# LAUNCHXL-F28379D_6.net
KiCad netlist of a schematic drawn in Altium Designer
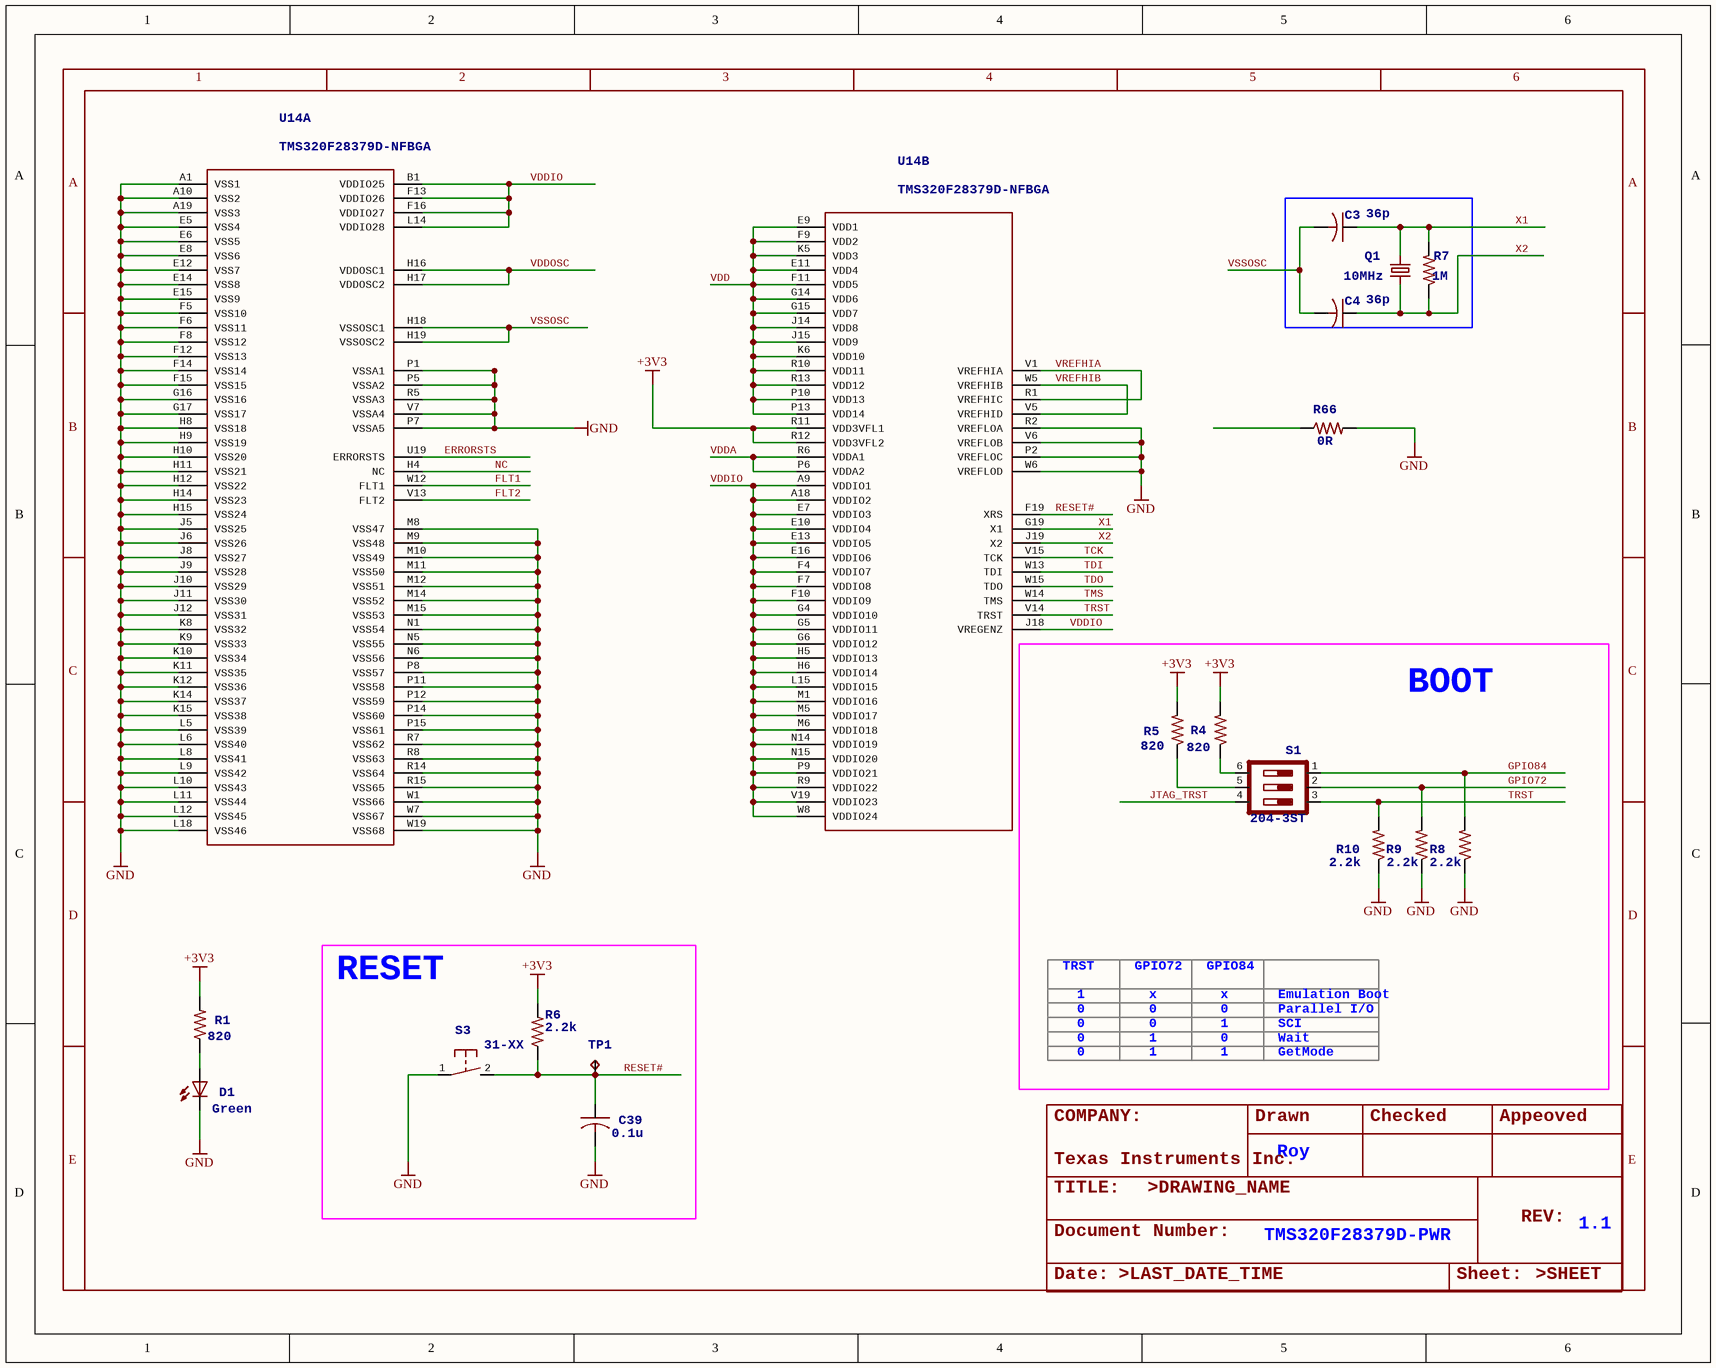
[diagram p0: LAUNCHXL-F28379D_6.SchDoc]

(export (version "E")
  (design (tool "Eeschema 10.0.6"))
  (components
    (comp (ref "C3")
      (value "36p")
      (footprint "C0402")
      (description "<B>CAPACITOR</B>, American symbol")
      (libsource (lib "rcl") (part "C-USC0402"))
    )
    (comp (ref "C4")
      (value "36p")
      (footprint "C0402")
      (description "<B>CAPACITOR</B>, American symbol")
      (libsource (lib "rcl") (part "C-USC0402"))
    )
    (comp (ref "C39")
      (value "0.1u")
      (footprint "C0402")
      (description "<B>CAPACITOR</B>, American symbol")
      (libsource (lib "rcl") (part "C-USC0402"))
    )
    (comp (ref "D1")
      (value "Green")
      (footprint "CHIP-LED0603")
      (libsource (lib "led") (part "LEDCHIP-LED0603"))
    )
    (comp (ref "Q1")
      (value "10MHz")
      (footprint "HC49/S")
      (description "<b>CRYSTAL</b>")
      (libsource (lib "crystal") (part "CRYSTALHC49S"))
    )
    (comp (ref "R1")
      (value "820")
      (footprint "R0402")
      (description "<B>RESISTOR</B>, American symbol")
      (libsource (lib "rcl") (part "R-US_R0402"))
    )
    (comp (ref "R4")
      (value "820")
      (footprint "R0402")
      (description "<B>RESISTOR</B>, American symbol")
      (libsource (lib "rcl") (part "R-US_R0402"))
    )
    (comp (ref "R5")
      (value "820")
      (footprint "R0402")
      (description "<B>RESISTOR</B>, American symbol")
      (libsource (lib "rcl") (part "R-US_R0402"))
    )
    (comp (ref "R6")
      (value "2.2k")
      (footprint "R0402")
      (description "<B>RESISTOR</B>, American symbol")
      (libsource (lib "rcl") (part "R-US_R0402"))
    )
    (comp (ref "R7")
      (value "1M")
      (footprint "R0402")
      (description "<B>RESISTOR</B>, American symbol")
      (libsource (lib "rcl") (part "R-US_R0402"))
    )
    (comp (ref "R8")
      (value "2.2k")
      (footprint "R0402")
      (description "<B>RESISTOR</B>, American symbol")
      (libsource (lib "rcl") (part "R-US_R0402"))
    )
    (comp (ref "R9")
      (value "2.2k")
      (footprint "R0402")
      (description "<B>RESISTOR</B>, American symbol")
      (libsource (lib "rcl") (part "R-US_R0402"))
    )
    (comp (ref "R10")
      (value "2.2k")
      (footprint "R0402")
      (description "<B>RESISTOR</B>, American symbol")
      (libsource (lib "rcl") (part "R-US_R0402"))
    )
    (comp (ref "R66")
      (value "0R")
      (footprint "R0402")
      (description "<B>RESISTOR</B>, American symbol")
      (libsource (lib "rcl") (part "R-US_R0402"))
    )
    (comp (ref "S1")
      (value "204-3ST")
      (footprint "CTS-219-03")
      (libsource (lib "switch-dil") (part "219-03*"))
    )
    (comp (ref "S3")
      (value "31-XX")
      (footprint "B3F-31XX")
      (description "<b>OMRON SWITCH</b>")
      (libsource (lib "switch-omron") (part "31-XX"))
    )
    (comp (ref "TP1")
      (value "TESTPAD_TPB1,27")
      (footprint "TESTPAD_B1,27")
      (description "<b>Test pad</b>")
      (libsource (lib "RF430FRL152H_EVM_a") (part "TESTPAD_TPB1,27"))
    )
    (comp (ref "U14")
      (value "TMS320F28379D-NFBGA")
      (footprint "BGA_F28079")
      (libsource (lib "F28379") (part "TMS320F28379D-NFBGA"))
    )
  )
  (nets
    (net (code "1") (name "+3V3") (class "Default")
      (node (ref "R1") (pin "2") (pinfunction "2_2") (pintype "passive"))
      (node (ref "R4") (pin "2") (pinfunction "2_2") (pintype "passive"))
      (node (ref "R5") (pin "2") (pinfunction "2_2") (pintype "passive"))
      (node (ref "R6") (pin "2") (pinfunction "2_2") (pintype "passive"))
      (node (ref "U14") (pin "R11") (pinfunction "VDD3VFL1_R11") (pintype "passive"))
      (node (ref "U14") (pin "R12") (pinfunction "VDD3VFL2_R12") (pintype "passive"))
    )
    (net (code "2") (name "/ERRORSTS") (class "Default")
      (node (ref "U14") (pin "U19") (pinfunction "ERRORSTS_U19") (pintype "passive"))
    )
    (net (code "3") (name "/FLT1") (class "Default")
      (node (ref "U14") (pin "W12") (pinfunction "FLT1_W12") (pintype "passive"))
    )
    (net (code "4") (name "/FLT2") (class "Default")
      (node (ref "U14") (pin "V13") (pinfunction "FLT2_V13") (pintype "passive"))
    )
    (net (code "5") (name "/GPIO72") (class "Default")
      (node (ref "R9") (pin "2") (pinfunction "2_2") (pintype "passive"))
      (node (ref "S1") (pin "2") (pinfunction "2_2") (pintype "passive"))
    )
    (net (code "6") (name "/GPIO84") (class "Default")
      (node (ref "R8") (pin "2") (pinfunction "2_2") (pintype "passive"))
      (node (ref "S1") (pin "1") (pinfunction "1_1") (pintype "passive"))
    )
    (net (code "7") (name "/JTAG_TRST") (class "Default")
      (node (ref "S1") (pin "4") (pinfunction "4_4") (pintype "passive"))
    )
    (net (code "8") (name "/NC") (class "Default")
      (node (ref "U14") (pin "H4") (pinfunction "NC_H4") (pintype "passive"))
    )
    (net (code "9") (name "/RESET#") (class "Default")
      (node (ref "C39") (pin "1") (pinfunction "1_1") (pintype "passive"))
      (node (ref "R6") (pin "1") (pinfunction "1_1") (pintype "passive"))
      (node (ref "S3") (pin "2") (pinfunction "S_2") (pintype "passive"))
      (node (ref "TP1") (pin "TP") (pinfunction "TP_TP") (pintype "passive"))
      (node (ref "U14") (pin "F19") (pinfunction "XRS_F19") (pintype "passive"))
    )
    (net (code "10") (name "/TCK") (class "Default")
      (node (ref "U14") (pin "V15") (pinfunction "TCK_V15") (pintype "passive"))
    )
    (net (code "11") (name "/TDI") (class "Default")
      (node (ref "U14") (pin "W13") (pinfunction "TDI_W13") (pintype "passive"))
    )
    (net (code "12") (name "/TDO") (class "Default")
      (node (ref "U14") (pin "W15") (pinfunction "TDO_W15") (pintype "passive"))
    )
    (net (code "13") (name "/TMS") (class "Default")
      (node (ref "U14") (pin "W14") (pinfunction "TMS_W14") (pintype "passive"))
    )
    (net (code "14") (name "/TRST") (class "Default")
      (node (ref "R10") (pin "2") (pinfunction "2_2") (pintype "passive"))
      (node (ref "S1") (pin "3") (pinfunction "3_3") (pintype "passive"))
      (node (ref "U14") (pin "V14") (pinfunction "TRST_V14") (pintype "passive"))
    )
    (net (code "15") (name "/VDD") (class "Default")
      (node (ref "U14") (pin "E11") (pinfunction "VDD4_E11") (pintype "passive"))
      (node (ref "U14") (pin "E9") (pinfunction "VDD1_E9") (pintype "passive"))
      (node (ref "U14") (pin "F11") (pinfunction "VDD5_F11") (pintype "passive"))
      (node (ref "U14") (pin "F9") (pinfunction "VDD2_F9") (pintype "passive"))
      (node (ref "U14") (pin "G14") (pinfunction "VDD6_G14") (pintype "passive"))
      (node (ref "U14") (pin "G15") (pinfunction "VDD7_G15") (pintype "passive"))
      (node (ref "U14") (pin "J14") (pinfunction "VDD8_J14") (pintype "passive"))
      (node (ref "U14") (pin "J15") (pinfunction "VDD9_J15") (pintype "passive"))
      (node (ref "U14") (pin "K5") (pinfunction "VDD3_K5") (pintype "passive"))
      (node (ref "U14") (pin "K6") (pinfunction "VDD10_K6") (pintype "passive"))
      (node (ref "U14") (pin "P10") (pinfunction "VDD13_P10") (pintype "passive"))
      (node (ref "U14") (pin "P13") (pinfunction "VDD14_P13") (pintype "passive"))
      (node (ref "U14") (pin "R10") (pinfunction "VDD11_R10") (pintype "passive"))
      (node (ref "U14") (pin "R13") (pinfunction "VDD12_R13") (pintype "passive"))
    )
    (net (code "16") (name "/VDDA") (class "Default")
      (node (ref "U14") (pin "P6") (pinfunction "VDDA2_P6") (pintype "passive"))
      (node (ref "U14") (pin "R6") (pinfunction "VDDA1_R6") (pintype "passive"))
    )
    (net (code "17") (name "/VDDIO") (class "Default")
      (node (ref "U14") (pin "A18") (pinfunction "VDDIO2_A18") (pintype "passive"))
      (node (ref "U14") (pin "A9") (pinfunction "VDDIO1_A9") (pintype "passive"))
      (node (ref "U14") (pin "B1") (pinfunction "VDDIO25_B1") (pintype "passive"))
      (node (ref "U14") (pin "E10") (pinfunction "VDDIO4_E10") (pintype "passive"))
      (node (ref "U14") (pin "E13") (pinfunction "VDDIO5_E13") (pintype "passive"))
      (node (ref "U14") (pin "E16") (pinfunction "VDDIO6_E16") (pintype "passive"))
      (node (ref "U14") (pin "E7") (pinfunction "VDDIO3_E7") (pintype "passive"))
      (node (ref "U14") (pin "F10") (pinfunction "VDDIO9_F10") (pintype "passive"))
      (node (ref "U14") (pin "F13") (pinfunction "VDDIO26_F13") (pintype "passive"))
      (node (ref "U14") (pin "F16") (pinfunction "VDDIO27_F16") (pintype "passive"))
      (node (ref "U14") (pin "F4") (pinfunction "VDDIO7_F4") (pintype "passive"))
      (node (ref "U14") (pin "F7") (pinfunction "VDDIO8_F7") (pintype "passive"))
      (node (ref "U14") (pin "G4") (pinfunction "VDDIO10_G4") (pintype "passive"))
      (node (ref "U14") (pin "G5") (pinfunction "VDDIO11_G5") (pintype "passive"))
      (node (ref "U14") (pin "G6") (pinfunction "VDDIO12_G6") (pintype "passive"))
      (node (ref "U14") (pin "H5") (pinfunction "VDDIO13_H5") (pintype "passive"))
      (node (ref "U14") (pin "H6") (pinfunction "VDDIO14_H6") (pintype "passive"))
      (node (ref "U14") (pin "J18") (pinfunction "VREGENZ_J18") (pintype "passive"))
      (node (ref "U14") (pin "L14") (pinfunction "VDDIO28_L14") (pintype "passive"))
      (node (ref "U14") (pin "L15") (pinfunction "VDDIO15_L15") (pintype "passive"))
      (node (ref "U14") (pin "M1") (pinfunction "VDDIO16_M1") (pintype "passive"))
      (node (ref "U14") (pin "M5") (pinfunction "VDDIO17_M5") (pintype "passive"))
      (node (ref "U14") (pin "M6") (pinfunction "VDDIO18_M6") (pintype "passive"))
      (node (ref "U14") (pin "N14") (pinfunction "VDDIO19_N14") (pintype "passive"))
      (node (ref "U14") (pin "N15") (pinfunction "VDDIO20_N15") (pintype "passive"))
      (node (ref "U14") (pin "P9") (pinfunction "VDDIO21_P9") (pintype "passive"))
      (node (ref "U14") (pin "R9") (pinfunction "VDDIO22_R9") (pintype "passive"))
      (node (ref "U14") (pin "V19") (pinfunction "VDDIO23_V19") (pintype "passive"))
      (node (ref "U14") (pin "W8") (pinfunction "VDDIO24_W8") (pintype "passive"))
    )
    (net (code "18") (name "/VDDOSC") (class "Default")
      (node (ref "U14") (pin "H16") (pinfunction "VDDOSC1_H16") (pintype "passive"))
      (node (ref "U14") (pin "H17") (pinfunction "VDDOSC2_H17") (pintype "passive"))
    )
    (net (code "19") (name "/VREFHIA") (class "Default")
      (node (ref "U14") (pin "R1") (pinfunction "VREFHIC_R1") (pintype "passive"))
      (node (ref "U14") (pin "V1") (pinfunction "VREFHIA_V1") (pintype "passive"))
    )
    (net (code "20") (name "/VREFHIB") (class "Default")
      (node (ref "U14") (pin "V5") (pinfunction "VREFHID_V5") (pintype "passive"))
      (node (ref "U14") (pin "W5") (pinfunction "VREFHIB_W5") (pintype "passive"))
    )
    (net (code "21") (name "/VSSOSC") (class "Default")
      (node (ref "C3") (pin "2") (pinfunction "2_2") (pintype "passive"))
      (node (ref "C4") (pin "2") (pinfunction "2_2") (pintype "passive"))
      (node (ref "U14") (pin "H18") (pinfunction "VSSOSC1_H18") (pintype "passive"))
      (node (ref "U14") (pin "H19") (pinfunction "VSSOSC2_H19") (pintype "passive"))
    )
    (net (code "22") (name "/X1") (class "Default")
      (node (ref "C3") (pin "1") (pinfunction "1_1") (pintype "passive"))
      (node (ref "Q1") (pin "2") (pinfunction "2_2") (pintype "passive"))
      (node (ref "R7") (pin "2") (pinfunction "2_2") (pintype "passive"))
      (node (ref "U14") (pin "G19") (pinfunction "X1_G19") (pintype "passive"))
    )
    (net (code "23") (name "/X2") (class "Default")
      (node (ref "C4") (pin "1") (pinfunction "1_1") (pintype "passive"))
      (node (ref "Q1") (pin "1") (pinfunction "1_1") (pintype "passive"))
      (node (ref "R7") (pin "1") (pinfunction "1_1") (pintype "passive"))
      (node (ref "U14") (pin "J19") (pinfunction "X2_J19") (pintype "passive"))
    )
    (net (code "24") (name "GND") (class "Default")
      (node (ref "C39") (pin "2") (pinfunction "2_2") (pintype "passive"))
      (node (ref "D1") (pin "C") (pinfunction "C_C") (pintype "passive"))
      (node (ref "R10") (pin "1") (pinfunction "1_1") (pintype "passive"))
      (node (ref "R66") (pin "2") (pinfunction "2_2") (pintype "passive"))
      (node (ref "R8") (pin "1") (pinfunction "1_1") (pintype "passive"))
      (node (ref "R9") (pin "1") (pinfunction "1_1") (pintype "passive"))
      (node (ref "S3") (pin "1") (pinfunction "P_1") (pintype "passive"))
      (node (ref "U14") (pin "A1") (pinfunction "VSS1_A1") (pintype "passive"))
      (node (ref "U14") (pin "A10") (pinfunction "VSS2_A10") (pintype "passive"))
      (node (ref "U14") (pin "A19") (pinfunction "VSS3_A19") (pintype "passive"))
      (node (ref "U14") (pin "E12") (pinfunction "VSS7_E12") (pintype "passive"))
      (node (ref "U14") (pin "E14") (pinfunction "VSS8_E14") (pintype "passive"))
      (node (ref "U14") (pin "E15") (pinfunction "VSS9_E15") (pintype "passive"))
      (node (ref "U14") (pin "E5") (pinfunction "VSS4_E5") (pintype "passive"))
      (node (ref "U14") (pin "E6") (pinfunction "VSS5_E6") (pintype "passive"))
      (node (ref "U14") (pin "E8") (pinfunction "VSS6_E8") (pintype "passive"))
      (node (ref "U14") (pin "F12") (pinfunction "VSS13_F12") (pintype "passive"))
      (node (ref "U14") (pin "F14") (pinfunction "VSS14_F14") (pintype "passive"))
      (node (ref "U14") (pin "F15") (pinfunction "VSS15_F15") (pintype "passive"))
      (node (ref "U14") (pin "F5") (pinfunction "VSS10_F5") (pintype "passive"))
      (node (ref "U14") (pin "F6") (pinfunction "VSS11_F6") (pintype "passive"))
      (node (ref "U14") (pin "F8") (pinfunction "VSS12_F8") (pintype "passive"))
      (node (ref "U14") (pin "G16") (pinfunction "VSS16_G16") (pintype "passive"))
      (node (ref "U14") (pin "G17") (pinfunction "VSS17_G17") (pintype "passive"))
      (node (ref "U14") (pin "H10") (pinfunction "VSS20_H10") (pintype "passive"))
      (node (ref "U14") (pin "H11") (pinfunction "VSS21_H11") (pintype "passive"))
      (node (ref "U14") (pin "H12") (pinfunction "VSS22_H12") (pintype "passive"))
      (node (ref "U14") (pin "H14") (pinfunction "VSS23_H14") (pintype "passive"))
      (node (ref "U14") (pin "H15") (pinfunction "VSS24_H15") (pintype "passive"))
      (node (ref "U14") (pin "H8") (pinfunction "VSS18_H8") (pintype "passive"))
      (node (ref "U14") (pin "H9") (pinfunction "VSS19_H9") (pintype "passive"))
      (node (ref "U14") (pin "J10") (pinfunction "VSS29_J10") (pintype "passive"))
      (node (ref "U14") (pin "J11") (pinfunction "VSS30_J11") (pintype "passive"))
      (node (ref "U14") (pin "J12") (pinfunction "VSS31_J12") (pintype "passive"))
      (node (ref "U14") (pin "J5") (pinfunction "VSS25_J5") (pintype "passive"))
      (node (ref "U14") (pin "J6") (pinfunction "VSS26_J6") (pintype "passive"))
      (node (ref "U14") (pin "J8") (pinfunction "VSS27_J8") (pintype "passive"))
      (node (ref "U14") (pin "J9") (pinfunction "VSS28_J9") (pintype "passive"))
      (node (ref "U14") (pin "K10") (pinfunction "VSS34_K10") (pintype "passive"))
      (node (ref "U14") (pin "K11") (pinfunction "VSS35_K11") (pintype "passive"))
      (node (ref "U14") (pin "K12") (pinfunction "VSS36_K12") (pintype "passive"))
      (node (ref "U14") (pin "K14") (pinfunction "VSS37_K14") (pintype "passive"))
      (node (ref "U14") (pin "K15") (pinfunction "VSS38_K15") (pintype "passive"))
      (node (ref "U14") (pin "K8") (pinfunction "VSS32_K8") (pintype "passive"))
      (node (ref "U14") (pin "K9") (pinfunction "VSS33_K9") (pintype "passive"))
      (node (ref "U14") (pin "L10") (pinfunction "VSS43_L10") (pintype "passive"))
      (node (ref "U14") (pin "L11") (pinfunction "VSS44_L11") (pintype "passive"))
      (node (ref "U14") (pin "L12") (pinfunction "VSS45_L12") (pintype "passive"))
      (node (ref "U14") (pin "L18") (pinfunction "VSS46_L18") (pintype "passive"))
      (node (ref "U14") (pin "L5") (pinfunction "VSS39_L5") (pintype "passive"))
      (node (ref "U14") (pin "L6") (pinfunction "VSS40_L6") (pintype "passive"))
      (node (ref "U14") (pin "L8") (pinfunction "VSS41_L8") (pintype "passive"))
      (node (ref "U14") (pin "L9") (pinfunction "VSS42_L9") (pintype "passive"))
      (node (ref "U14") (pin "M10") (pinfunction "VSS49_M10") (pintype "passive"))
      (node (ref "U14") (pin "M11") (pinfunction "VSS50_M11") (pintype "passive"))
      (node (ref "U14") (pin "M12") (pinfunction "VSS51_M12") (pintype "passive"))
      (node (ref "U14") (pin "M14") (pinfunction "VSS52_M14") (pintype "passive"))
      (node (ref "U14") (pin "M15") (pinfunction "VSS53_M15") (pintype "passive"))
      (node (ref "U14") (pin "M8") (pinfunction "VSS47_M8") (pintype "passive"))
      (node (ref "U14") (pin "M9") (pinfunction "VSS48_M9") (pintype "passive"))
      (node (ref "U14") (pin "N1") (pinfunction "VSS54_N1") (pintype "passive"))
      (node (ref "U14") (pin "N5") (pinfunction "VSS55_N5") (pintype "passive"))
      (node (ref "U14") (pin "N6") (pinfunction "VSS56_N6") (pintype "passive"))
      (node (ref "U14") (pin "P1") (pinfunction "VSSA1_P1") (pintype "passive"))
      (node (ref "U14") (pin "P11") (pinfunction "VSS58_P11") (pintype "passive"))
      (node (ref "U14") (pin "P12") (pinfunction "VSS59_P12") (pintype "passive"))
      (node (ref "U14") (pin "P14") (pinfunction "VSS60_P14") (pintype "passive"))
      (node (ref "U14") (pin "P15") (pinfunction "VSS61_P15") (pintype "passive"))
      (node (ref "U14") (pin "P2") (pinfunction "VREFLOC_P2") (pintype "passive"))
      (node (ref "U14") (pin "P5") (pinfunction "VSSA2_P5") (pintype "passive"))
      (node (ref "U14") (pin "P7") (pinfunction "VSSA5_P7") (pintype "passive"))
      (node (ref "U14") (pin "P8") (pinfunction "VSS57_P8") (pintype "passive"))
      (node (ref "U14") (pin "R14") (pinfunction "VSS64_R14") (pintype "passive"))
      (node (ref "U14") (pin "R15") (pinfunction "VSS65_R15") (pintype "passive"))
      (node (ref "U14") (pin "R2") (pinfunction "VREFLOA_R2") (pintype "passive"))
      (node (ref "U14") (pin "R5") (pinfunction "VSSA3_R5") (pintype "passive"))
      (node (ref "U14") (pin "R7") (pinfunction "VSS62_R7") (pintype "passive"))
      (node (ref "U14") (pin "R8") (pinfunction "VSS63_R8") (pintype "passive"))
      (node (ref "U14") (pin "V6") (pinfunction "VREFLOB_V6") (pintype "passive"))
      (node (ref "U14") (pin "V7") (pinfunction "VSSA4_V7") (pintype "passive"))
      (node (ref "U14") (pin "W1") (pinfunction "VSS66_W1") (pintype "passive"))
      (node (ref "U14") (pin "W19") (pinfunction "VSS68_W19") (pintype "passive"))
      (node (ref "U14") (pin "W6") (pinfunction "VREFLOD_W6") (pintype "passive"))
      (node (ref "U14") (pin "W7") (pinfunction "VSS67_W7") (pintype "passive"))
    )
    (net (code "25") (name "Net-(D1-PadA)") (class "Default")
      (node (ref "D1") (pin "A") (pinfunction "A_A") (pintype "passive"))
      (node (ref "R1") (pin "1") (pinfunction "1_1") (pintype "passive"))
    )
    (net (code "26") (name "Net-(R4-Pad1)") (class "Default")
      (node (ref "R4") (pin "1") (pinfunction "1_1") (pintype "passive"))
      (node (ref "S1") (pin "6") (pinfunction "6_6") (pintype "passive"))
    )
    (net (code "27") (name "Net-(R5-Pad1)") (class "Default")
      (node (ref "R5") (pin "1") (pinfunction "1_1") (pintype "passive"))
      (node (ref "S1") (pin "5") (pinfunction "5_5") (pintype "passive"))
    )
    (net (code "28") (name "unconnected-(R66-Pad1)") (class "Default")
      (node (ref "R66") (pin "1") (pinfunction "1_1") (pintype "passive"))
    )
  )
)
